# -ZPanel.net
KiCad netlist of a schematic drawn in EAGLE
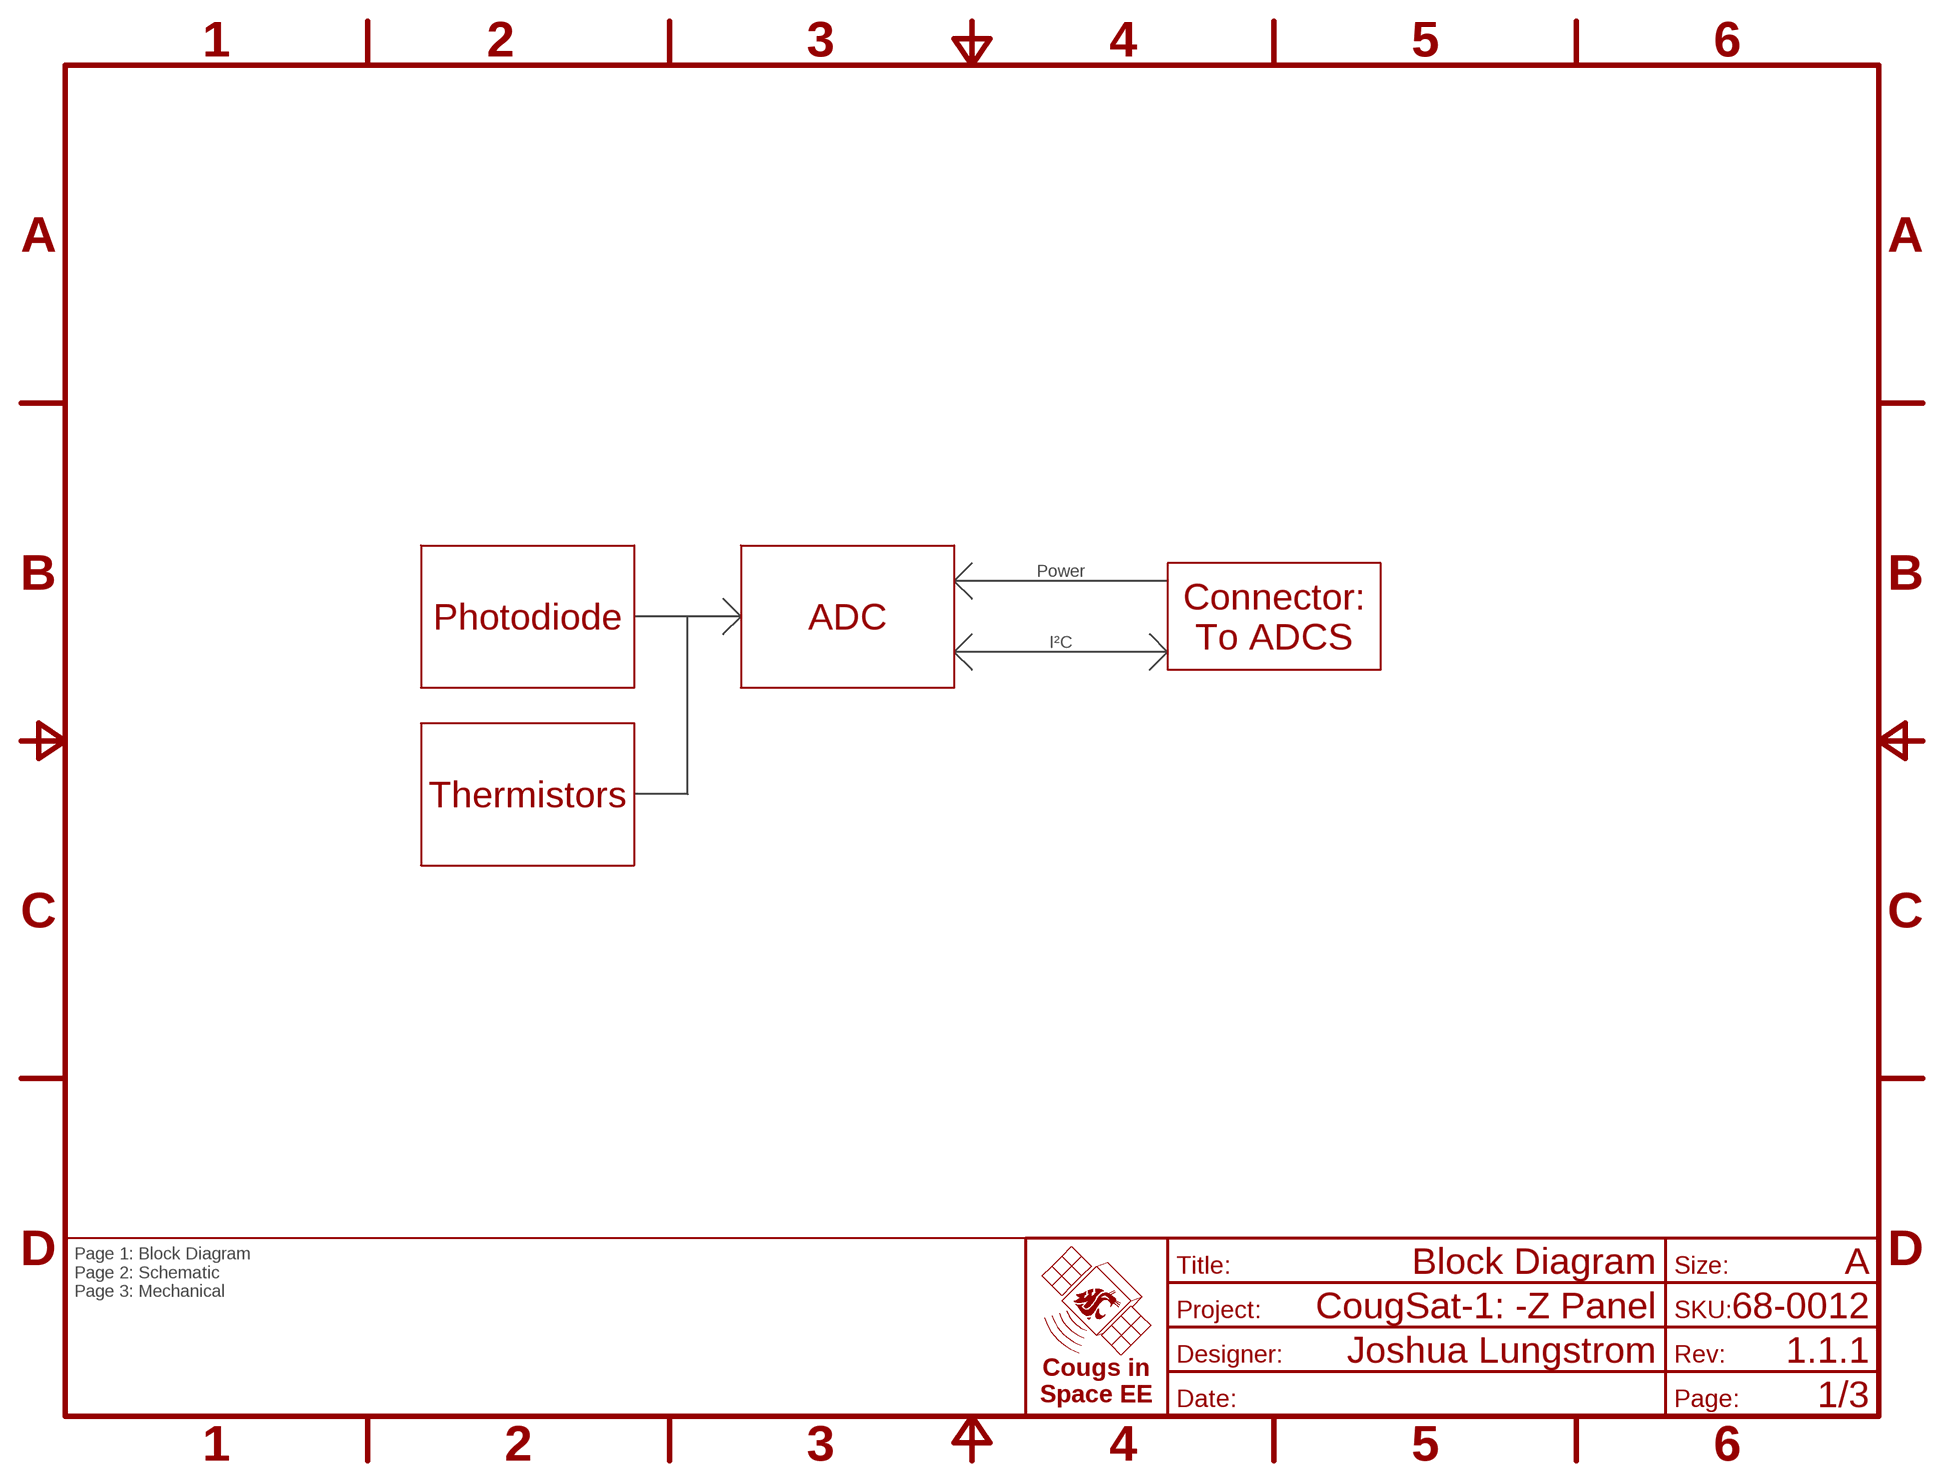
[diagram p0: schematic, sheet 1]
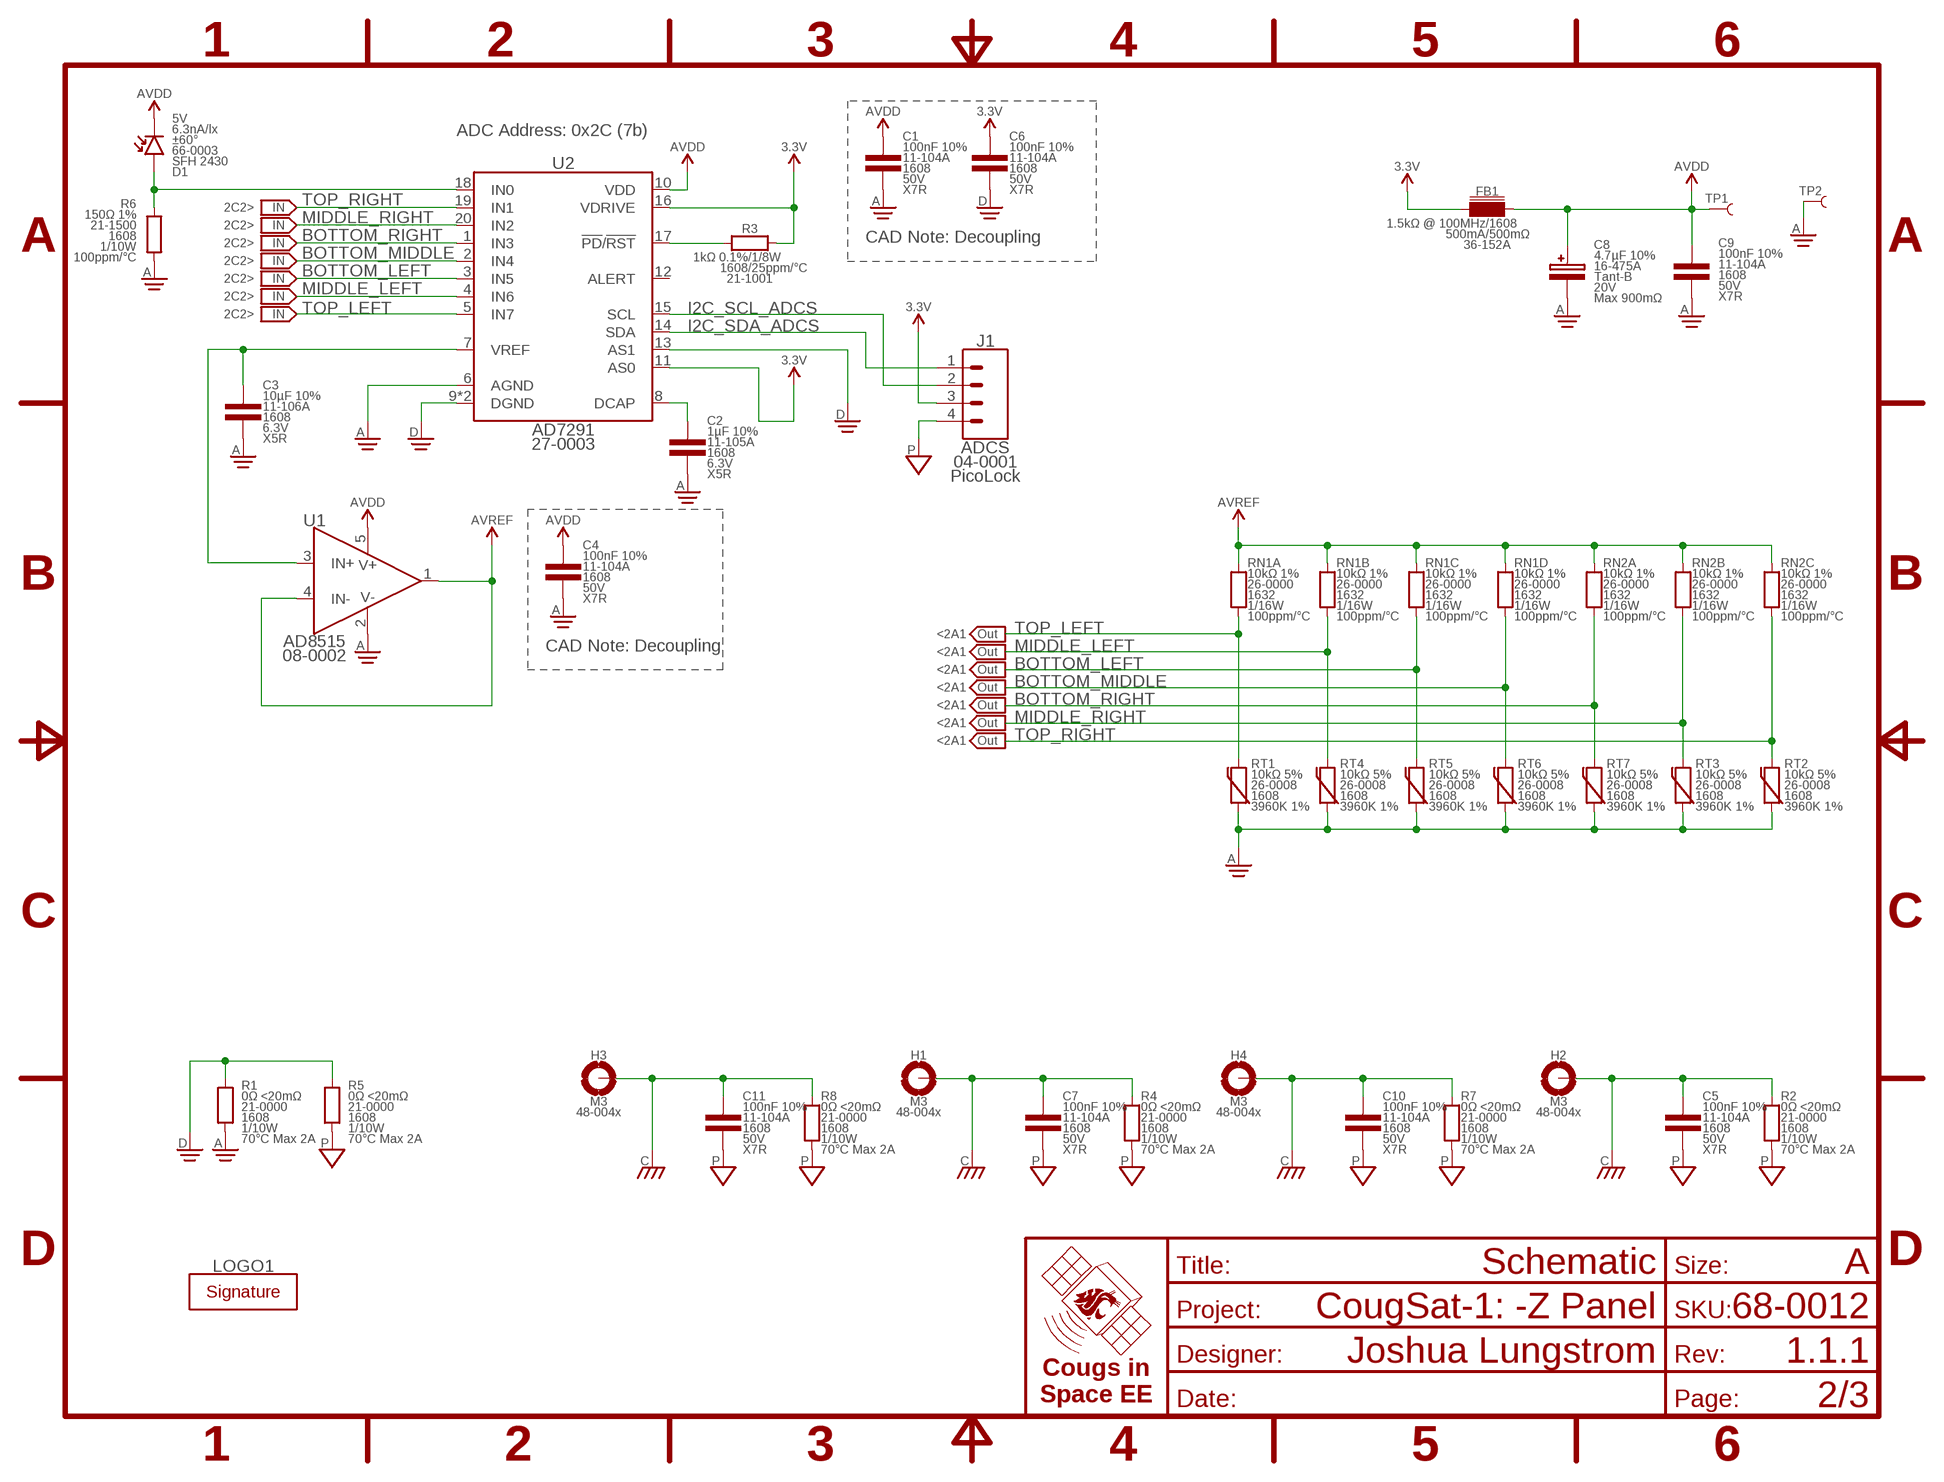
[diagram p1: schematic, sheet 2]
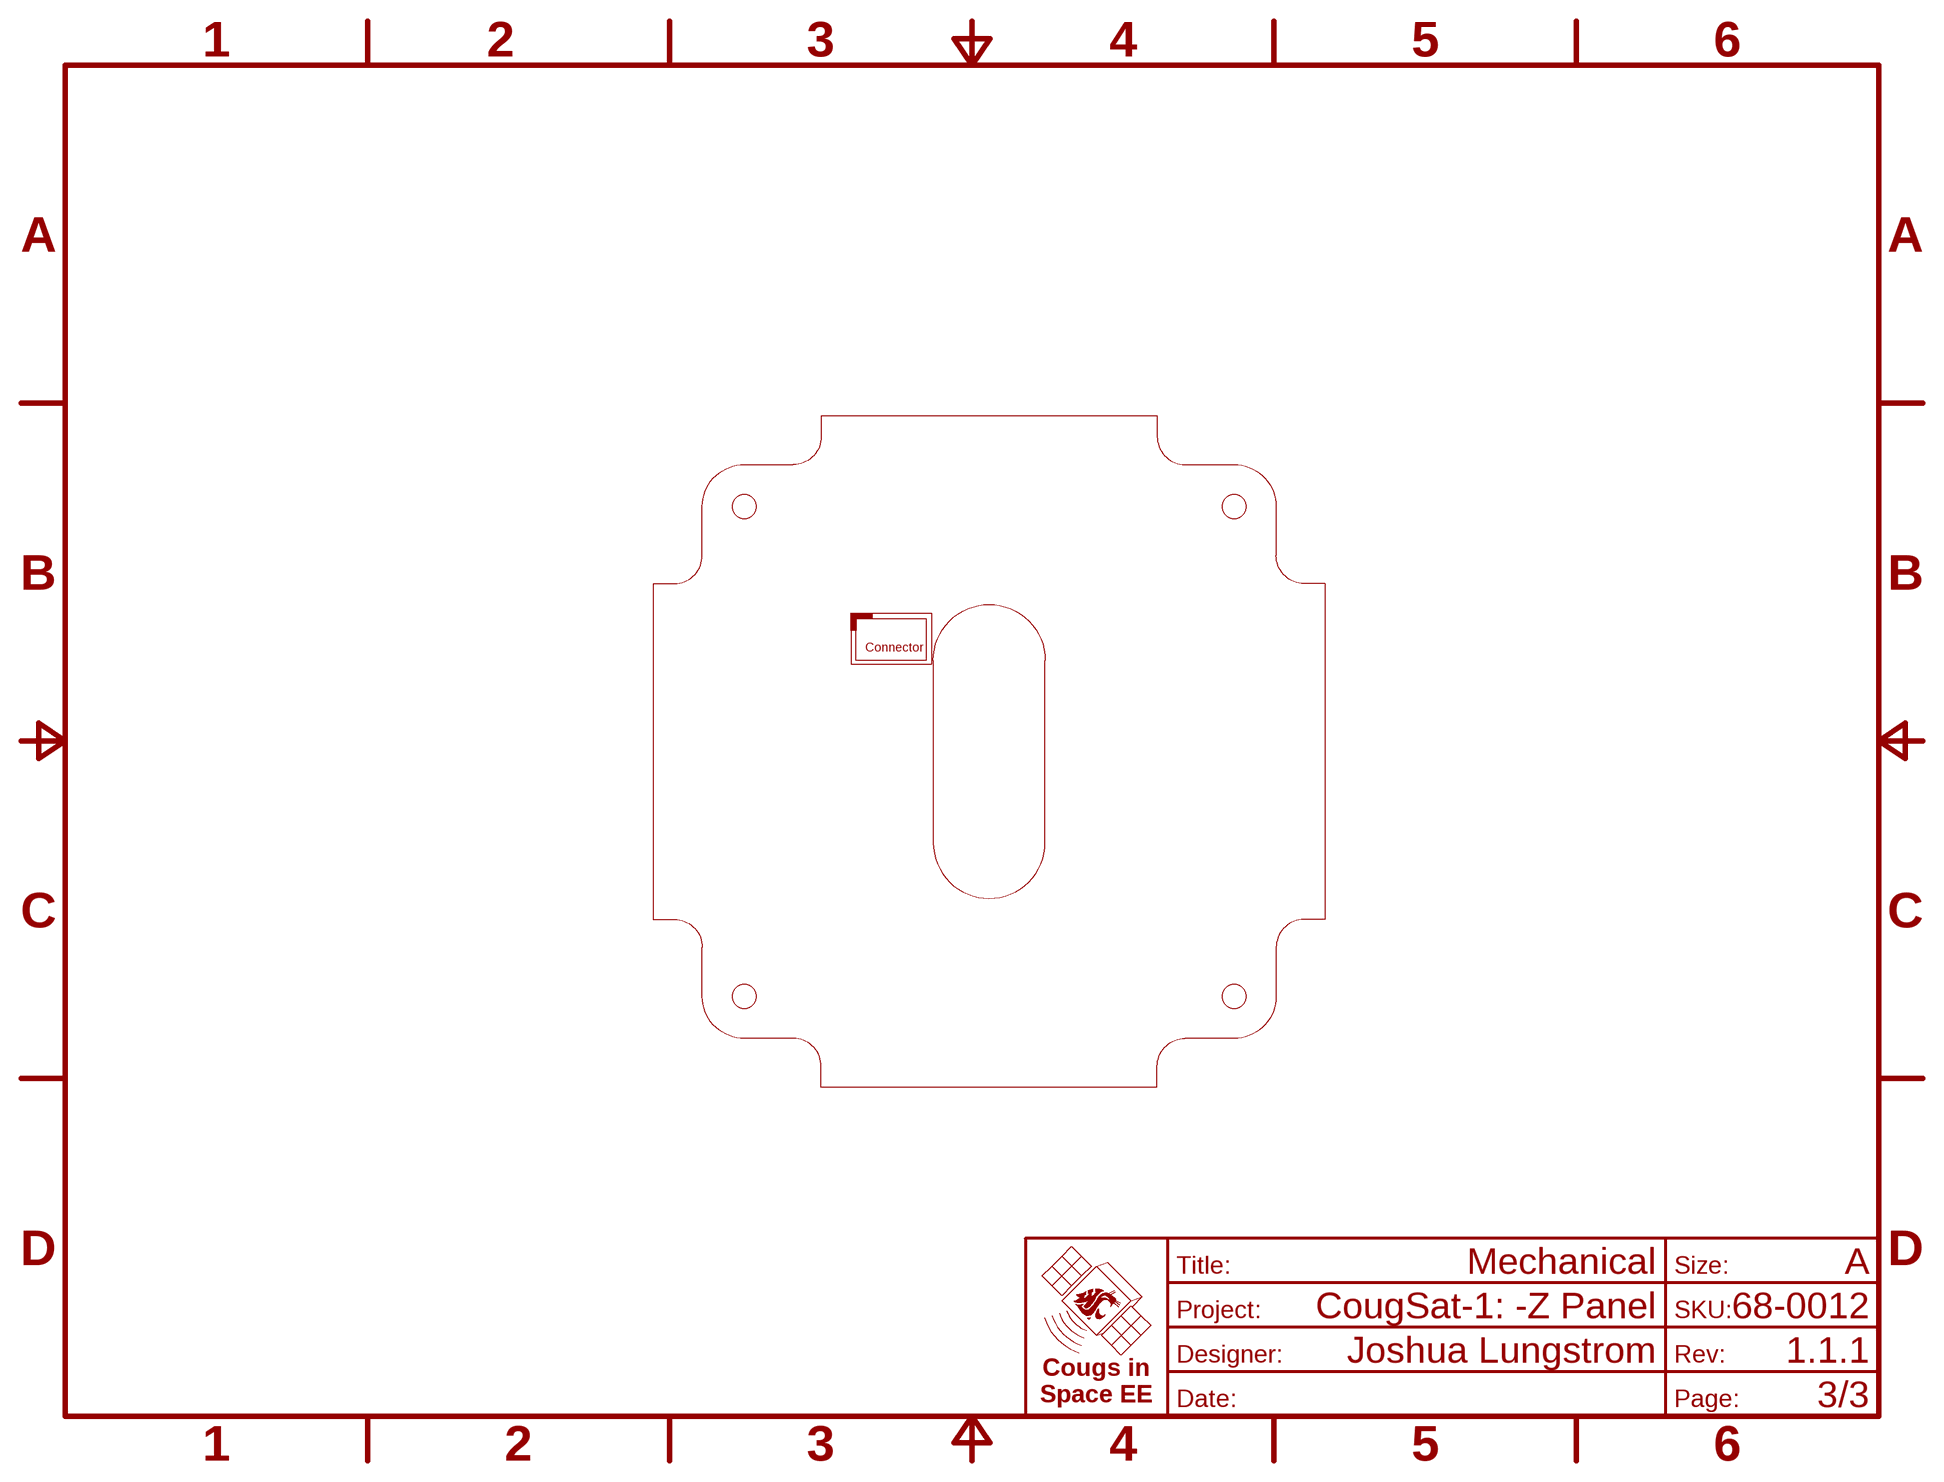
[diagram p2: schematic, sheet 3]

(export (version "E")
  (design (tool "Eeschema 10.0.6"))
  (components
    (comp (ref "C1")
      (value "100nF 10%")
      (footprint "eagle-import:1608")
      (fields
        (field (name "PACKAGE") "1608")
        (field (name "SKU") "11-104A")
        (field (name "TEMP") "X7R")
        (field (name "VOLTAGE") "50V")
      )
      (libsource (lib "eagle-import") (part "CAP-V-1608-100NF"))
    )
    (comp (ref "C2")
      (value "1µF 10%")
      (footprint "eagle-import:1608")
      (fields
        (field (name "PACKAGE") "1608")
        (field (name "SKU") "11-105A")
        (field (name "TEMP") "X5R")
        (field (name "VOLTAGE") "6.3V")
      )
      (libsource (lib "eagle-import") (part "CAP-V-1608-1UF"))
    )
    (comp (ref "C3")
      (value "10µF 10%")
      (footprint "eagle-import:1608")
      (fields
        (field (name "PACKAGE") "1608")
        (field (name "SKU") "11-106A")
        (field (name "TEMP") "X5R")
        (field (name "VOLTAGE") "6.3V")
      )
      (libsource (lib "eagle-import") (part "CAP-V-1608-10UF"))
    )
    (comp (ref "C4")
      (value "100nF 10%")
      (footprint "eagle-import:1608")
      (fields
        (field (name "PACKAGE") "1608")
        (field (name "SKU") "11-104A")
        (field (name "TEMP") "X7R")
        (field (name "VOLTAGE") "50V")
      )
      (libsource (lib "eagle-import") (part "CAP-V-1608-100NF"))
    )
    (comp (ref "C5")
      (value "100nF 10%")
      (footprint "eagle-import:1608")
      (fields
        (field (name "PACKAGE") "1608")
        (field (name "SKU") "11-104A")
        (field (name "TEMP") "X7R")
        (field (name "VOLTAGE") "50V")
      )
      (libsource (lib "eagle-import") (part "CAP-V-1608-100NF"))
    )
    (comp (ref "C6")
      (value "100nF 10%")
      (footprint "eagle-import:1608")
      (fields
        (field (name "PACKAGE") "1608")
        (field (name "SKU") "11-104A")
        (field (name "TEMP") "X7R")
        (field (name "VOLTAGE") "50V")
      )
      (libsource (lib "eagle-import") (part "CAP-V-1608-100NF"))
    )
    (comp (ref "C7")
      (value "100nF 10%")
      (footprint "eagle-import:1608")
      (fields
        (field (name "PACKAGE") "1608")
        (field (name "SKU") "11-104A")
        (field (name "TEMP") "X7R")
        (field (name "VOLTAGE") "50V")
      )
      (libsource (lib "eagle-import") (part "CAP-V-1608-100NF"))
    )
    (comp (ref "C8")
      (value "4.7µF 10%")
      (footprint "eagle-import:4028-POL")
      (fields
        (field (name "ESR") "Max 900mΩ")
        (field (name "PACKAGE") "Tant-B")
        (field (name "SKU") "16-475A")
        (field (name "VOLTAGE") "20V")
      )
      (libsource (lib "eagle-import") (part "CAP-POL-V-4028-4.7UF"))
    )
    (comp (ref "C9")
      (value "100nF 10%")
      (footprint "eagle-import:1608")
      (fields
        (field (name "PACKAGE") "1608")
        (field (name "SKU") "11-104A")
        (field (name "TEMP") "X7R")
        (field (name "VOLTAGE") "50V")
      )
      (libsource (lib "eagle-import") (part "CAP-V-1608-100NF"))
    )
    (comp (ref "C10")
      (value "100nF 10%")
      (footprint "eagle-import:1608")
      (fields
        (field (name "PACKAGE") "1608")
        (field (name "SKU") "11-104A")
        (field (name "TEMP") "X7R")
        (field (name "VOLTAGE") "50V")
      )
      (libsource (lib "eagle-import") (part "CAP-V-1608-100NF"))
    )
    (comp (ref "C11")
      (value "100nF 10%")
      (footprint "eagle-import:1608")
      (fields
        (field (name "PACKAGE") "1608")
        (field (name "SKU") "11-104A")
        (field (name "TEMP") "X7R")
        (field (name "VOLTAGE") "50V")
      )
      (libsource (lib "eagle-import") (part "CAP-V-1608-100NF"))
    )
    (comp (ref "D1")
      (value "SFH 2430")
      (footprint "eagle-import:SFH2430")
      (fields
        (field (name "SKU") "66-0003")
        (field (name "SENSITIVITY") "6.3nA/lx")
        (field (name "VR") "5V")
        (field (name "HALF_ANGLE") "±60°")
      )
      (libsource (lib "eagle-import") (part "PHOTODIODE-SFH2430"))
    )
    (comp (ref "FB1")
      (value "1.5kΩ @ 100MHz")
      (footprint "eagle-import:1608")
      (fields
        (field (name "CURRENT") "500mA")
        (field (name "DCR") "500mΩ")
        (field (name "PACKAGE") "1608")
        (field (name "SKU") "36-152A")
      )
      (libsource (lib "eagle-import") (part "CHOKE-H-1608-1.5K"))
    )
    (comp (ref "H1")
      (value "M3")
      (footprint "eagle-import:MOUNTING_HOLE-3.3")
      (fields (field (name "SKU") "48-004x"))
      (libsource (lib "eagle-import") (part "MOUNTING_HOLE-3.3"))
    )
    (comp (ref "H2")
      (value "M3")
      (footprint "eagle-import:MOUNTING_HOLE-3.3")
      (fields (field (name "SKU") "48-004x"))
      (libsource (lib "eagle-import") (part "MOUNTING_HOLE-3.3"))
    )
    (comp (ref "H3")
      (value "M3")
      (footprint "eagle-import:MOUNTING_HOLE-3.3")
      (fields (field (name "SKU") "48-004x"))
      (libsource (lib "eagle-import") (part "MOUNTING_HOLE-3.3"))
    )
    (comp (ref "H4")
      (value "M3")
      (footprint "eagle-import:MOUNTING_HOLE-3.3")
      (fields (field (name "SKU") "48-004x"))
      (libsource (lib "eagle-import") (part "MOUNTING_HOLE-3.3"))
    )
    (comp (ref "J1")
      (value "ADCS")
      (footprint "eagle-import:PICOLOCK1.5-04")
      (fields (field (name "SKU") "04-0001") (field (name "PACKAGE") "PicoLock"))
      (libsource (lib "eagle-import") (part "1X04-PICOLOCK"))
    )
    (comp (ref "LOGO1")
      (value "SIGNATUREJOSH")
      (footprint "eagle-import:SIGN-JOSH")
      (libsource (lib "eagle-import") (part "SIGNATUREJOSH"))
    )
    (comp (ref "R1")
      (value "0Ω <20mΩ")
      (footprint "eagle-import:1608")
      (fields
        (field (name "PACKAGE") "1608")
        (field (name "POWER") "1/10W")
        (field (name "SKU") "21-0000")
        (field (name "TEMP") "70°C Max 2A")
      )
      (libsource (lib "eagle-import") (part "RES-V-1608-0"))
    )
    (comp (ref "R2")
      (value "0Ω <20mΩ")
      (footprint "eagle-import:1608")
      (fields
        (field (name "PACKAGE") "1608")
        (field (name "POWER") "1/10W")
        (field (name "SKU") "21-0000")
        (field (name "TEMP") "70°C Max 2A")
      )
      (libsource (lib "eagle-import") (part "RES-V-1608-0"))
    )
    (comp (ref "R3")
      (value "1kΩ 0.1%")
      (footprint "eagle-import:1608")
      (fields
        (field (name "PACKAGE") "1608")
        (field (name "POWER") "1/8W")
        (field (name "SKU") "21-1001")
        (field (name "TEMP") "25ppm/°C")
      )
      (libsource (lib "eagle-import") (part "RES-H-1608-1K"))
    )
    (comp (ref "R4")
      (value "0Ω <20mΩ")
      (footprint "eagle-import:1608")
      (fields
        (field (name "PACKAGE") "1608")
        (field (name "POWER") "1/10W")
        (field (name "SKU") "21-0000")
        (field (name "TEMP") "70°C Max 2A")
      )
      (libsource (lib "eagle-import") (part "RES-V-1608-0"))
    )
    (comp (ref "R5")
      (value "0Ω <20mΩ")
      (footprint "eagle-import:1608")
      (fields
        (field (name "PACKAGE") "1608")
        (field (name "POWER") "1/10W")
        (field (name "SKU") "21-0000")
        (field (name "TEMP") "70°C Max 2A")
      )
      (libsource (lib "eagle-import") (part "RES-V-1608-0"))
    )
    (comp (ref "R6")
      (value "150Ω 1%")
      (footprint "eagle-import:1608")
      (fields
        (field (name "PACKAGE") "1608")
        (field (name "POWER") "1/10W")
        (field (name "SKU") "21-1500")
        (field (name "TEMP") "100ppm/°C")
      )
      (libsource (lib "eagle-import") (part "RES-V-1608-150R"))
    )
    (comp (ref "R7")
      (value "0Ω <20mΩ")
      (footprint "eagle-import:1608")
      (fields
        (field (name "PACKAGE") "1608")
        (field (name "POWER") "1/10W")
        (field (name "SKU") "21-0000")
        (field (name "TEMP") "70°C Max 2A")
      )
      (libsource (lib "eagle-import") (part "RES-V-1608-0"))
    )
    (comp (ref "R8")
      (value "0Ω <20mΩ")
      (footprint "eagle-import:1608")
      (fields
        (field (name "PACKAGE") "1608")
        (field (name "POWER") "1/10W")
        (field (name "SKU") "21-0000")
        (field (name "TEMP") "70°C Max 2A")
      )
      (libsource (lib "eagle-import") (part "RES-V-1608-0"))
    )
    (comp (ref "RN1")
      (value "10kΩ 1%")
      (footprint "eagle-import:1632")
      (fields
        (field (name "PACKAGE") "1632")
        (field (name "POWER") "1/16W")
        (field (name "SKU") "26-0000")
        (field (name "TEMP") "100ppm/°C")
      )
      (libsource (lib "eagle-import") (part "RES-4-V-1632-10K"))
    )
    (comp (ref "RN2")
      (value "10kΩ 1%")
      (footprint "eagle-import:1632")
      (fields
        (field (name "PACKAGE") "1632")
        (field (name "POWER") "1/16W")
        (field (name "SKU") "26-0000")
        (field (name "TEMP") "100ppm/°C")
      )
      (libsource (lib "eagle-import") (part "RES-4-V-1632-10K"))
    )
    (comp (ref "RT1")
      (value "10kΩ 5%")
      (footprint "eagle-import:1608")
      (fields
        (field (name "B2585") "3960K 1%")
        (field (name "PACKAGE") "1608")
        (field (name "SKU") "26-0008")
      )
      (libsource (lib "eagle-import") (part "THERMISTOR-V-1608-10K"))
    )
    (comp (ref "RT2")
      (value "10kΩ 5%")
      (footprint "eagle-import:1608")
      (fields
        (field (name "B2585") "3960K 1%")
        (field (name "PACKAGE") "1608")
        (field (name "SKU") "26-0008")
      )
      (libsource (lib "eagle-import") (part "THERMISTOR-V-1608-10K"))
    )
    (comp (ref "RT3")
      (value "10kΩ 5%")
      (footprint "eagle-import:1608")
      (fields
        (field (name "B2585") "3960K 1%")
        (field (name "PACKAGE") "1608")
        (field (name "SKU") "26-0008")
      )
      (libsource (lib "eagle-import") (part "THERMISTOR-V-1608-10K"))
    )
    (comp (ref "RT4")
      (value "10kΩ 5%")
      (footprint "eagle-import:1608")
      (fields
        (field (name "B2585") "3960K 1%")
        (field (name "PACKAGE") "1608")
        (field (name "SKU") "26-0008")
      )
      (libsource (lib "eagle-import") (part "THERMISTOR-V-1608-10K"))
    )
    (comp (ref "RT5")
      (value "10kΩ 5%")
      (footprint "eagle-import:1608")
      (fields
        (field (name "B2585") "3960K 1%")
        (field (name "PACKAGE") "1608")
        (field (name "SKU") "26-0008")
      )
      (libsource (lib "eagle-import") (part "THERMISTOR-V-1608-10K"))
    )
    (comp (ref "RT6")
      (value "10kΩ 5%")
      (footprint "eagle-import:1608")
      (fields
        (field (name "B2585") "3960K 1%")
        (field (name "PACKAGE") "1608")
        (field (name "SKU") "26-0008")
      )
      (libsource (lib "eagle-import") (part "THERMISTOR-V-1608-10K"))
    )
    (comp (ref "RT7")
      (value "10kΩ 5%")
      (footprint "eagle-import:1608")
      (fields
        (field (name "B2585") "3960K 1%")
        (field (name "PACKAGE") "1608")
        (field (name "SKU") "26-0008")
      )
      (libsource (lib "eagle-import") (part "THERMISTOR-V-1608-10K"))
    )
    (comp (ref "TP1")
      (value "TEST_POINT-THT-0.7")
      (footprint "eagle-import:THT-0.7")
      (libsource (lib "eagle-import") (part "TEST_POINT-THT-0.7"))
    )
    (comp (ref "TP2")
      (value "TEST_POINT-THT-0.7")
      (footprint "eagle-import:THT-0.7")
      (libsource (lib "eagle-import") (part "TEST_POINT-THT-0.7"))
    )
    (comp (ref "U1")
      (value "AD8515")
      (footprint "eagle-import:SOT23-5")
      (fields (field (name "SKU") "08-0002"))
      (libsource (lib "eagle-import") (part "OPAMP-1-AD8515"))
    )
    (comp (ref "U2")
      (value "AD7291")
      (footprint "eagle-import:QFN-20-4040")
      (fields (field (name "SKU") "27-0003"))
      (libsource (lib "eagle-import") (part "AD7291"))
    )
  )
  (nets
    (net (code "1") (name "3.3V") (class "Default")
      (node (ref "C6") (pin "1") (pinfunction "1_1") (pintype "passive"))
      (node (ref "FB1") (pin "1") (pinfunction "1_1") (pintype "passive"))
      (node (ref "J1") (pin "3") (pinfunction "3_3") (pintype "passive"))
      (node (ref "R3") (pin "2") (pinfunction "2_2") (pintype "passive"))
      (node (ref "U2") (pin "11") (pinfunction "AS0_11") (pintype "passive"))
      (node (ref "U2") (pin "16") (pinfunction "VDRIVE_16") (pintype "power_in"))
    )
    (net (code "2") (name "AGND") (class "Default")
      (node (ref "C1") (pin "2") (pinfunction "2_2") (pintype "passive"))
      (node (ref "C2") (pin "2") (pinfunction "2_2") (pintype "passive"))
      (node (ref "C3") (pin "2") (pinfunction "2_2") (pintype "passive"))
      (node (ref "C4") (pin "2") (pinfunction "2_2") (pintype "passive"))
      (node (ref "C8") (pin "C") (pinfunction "C_C") (pintype "passive"))
      (node (ref "C9") (pin "2") (pinfunction "2_2") (pintype "passive"))
      (node (ref "R1") (pin "1") (pinfunction "1_1") (pintype "passive"))
      (node (ref "R6") (pin "1") (pinfunction "1_1") (pintype "passive"))
      (node (ref "RT1") (pin "1") (pinfunction "1_1") (pintype "passive"))
      (node (ref "RT2") (pin "1") (pinfunction "1_1") (pintype "passive"))
      (node (ref "RT3") (pin "1") (pinfunction "1_1") (pintype "passive"))
      (node (ref "RT4") (pin "1") (pinfunction "1_1") (pintype "passive"))
      (node (ref "RT5") (pin "1") (pinfunction "1_1") (pintype "passive"))
      (node (ref "RT6") (pin "1") (pinfunction "1_1") (pintype "passive"))
      (node (ref "RT7") (pin "1") (pinfunction "1_1") (pintype "passive"))
      (node (ref "TP2") (pin "1") (pinfunction "1_1") (pintype "passive"))
      (node (ref "U1") (pin "2") (pinfunction "V-_2") (pintype "power_in"))
      (node (ref "U2") (pin "6") (pinfunction "AGND_6") (pintype "power_in"))
    )
    (net (code "3") (name "AVDD") (class "Default")
      (node (ref "C1") (pin "1") (pinfunction "1_1") (pintype "passive"))
      (node (ref "C4") (pin "1") (pinfunction "1_1") (pintype "passive"))
      (node (ref "C8") (pin "A") (pinfunction "A_A") (pintype "passive"))
      (node (ref "C9") (pin "1") (pinfunction "1_1") (pintype "passive"))
      (node (ref "D1") (pin "C") (pinfunction "C_C") (pintype "passive"))
      (node (ref "FB1") (pin "2") (pinfunction "2_2") (pintype "passive"))
      (node (ref "TP1") (pin "1") (pinfunction "1_1") (pintype "passive"))
      (node (ref "U1") (pin "5") (pinfunction "V+_5") (pintype "power_in"))
      (node (ref "U2") (pin "10") (pinfunction "VDD_10") (pintype "power_in"))
    )
    (net (code "4") (name "AVREF") (class "Default")
      (node (ref "RN1") (pin "5") (pinfunction "2_5") (pintype "passive"))
      (node (ref "RN1") (pin "6") (pinfunction "2_6") (pintype "passive"))
      (node (ref "RN1") (pin "7") (pinfunction "2_7") (pintype "passive"))
      (node (ref "RN1") (pin "8") (pinfunction "2_8") (pintype "passive"))
      (node (ref "RN2") (pin "6") (pinfunction "2_6") (pintype "passive"))
      (node (ref "RN2") (pin "7") (pinfunction "2_7") (pintype "passive"))
      (node (ref "RN2") (pin "8") (pinfunction "2_8") (pintype "passive"))
      (node (ref "U1") (pin "1") (pinfunction "OUT_1") (pintype "output"))
      (node (ref "U1") (pin "4") (pinfunction "IN-_4") (pintype "passive"))
    )
    (net (code "5") (name "BOTTOM_LEFT") (class "Default")
      (node (ref "RN1") (pin "3") (pinfunction "1_3") (pintype "passive"))
      (node (ref "RT5") (pin "2") (pinfunction "2_2") (pintype "passive"))
      (node (ref "U2") (pin "3") (pinfunction "IN5_3") (pintype "input"))
    )
    (net (code "6") (name "BOTTOM_MIDDLE") (class "Default")
      (node (ref "RN1") (pin "4") (pinfunction "1_4") (pintype "passive"))
      (node (ref "RT6") (pin "2") (pinfunction "2_2") (pintype "passive"))
      (node (ref "U2") (pin "2") (pinfunction "IN4_2") (pintype "input"))
    )
    (net (code "7") (name "BOTTOM_RIGHT") (class "Default")
      (node (ref "RN2") (pin "1") (pinfunction "1_1") (pintype "passive"))
      (node (ref "RT7") (pin "2") (pinfunction "2_2") (pintype "passive"))
      (node (ref "U2") (pin "1") (pinfunction "IN3_1") (pintype "input"))
    )
    (net (code "8") (name "CHASSIS") (class "Default")
      (node (ref "C10") (pin "1") (pinfunction "1_1") (pintype "passive"))
      (node (ref "C11") (pin "1") (pinfunction "1_1") (pintype "passive"))
      (node (ref "C5") (pin "1") (pinfunction "1_1") (pintype "passive"))
      (node (ref "C7") (pin "1") (pinfunction "1_1") (pintype "passive"))
      (node (ref "H1") (pin "1") (pinfunction "MOUNT_1") (pintype "passive"))
      (node (ref "H1") (pin "V1") (pinfunction "MOUNT_V1") (pintype "passive"))
      (node (ref "H1") (pin "V10") (pinfunction "MOUNT_V10") (pintype "passive"))
      (node (ref "H1") (pin "V2") (pinfunction "MOUNT_V2") (pintype "passive"))
      (node (ref "H1") (pin "V3") (pinfunction "MOUNT_V3") (pintype "passive"))
      (node (ref "H1") (pin "V4") (pinfunction "MOUNT_V4") (pintype "passive"))
      (node (ref "H1") (pin "V5") (pinfunction "MOUNT_V5") (pintype "passive"))
      (node (ref "H1") (pin "V6") (pinfunction "MOUNT_V6") (pintype "passive"))
      (node (ref "H1") (pin "V7") (pinfunction "MOUNT_V7") (pintype "passive"))
      (node (ref "H1") (pin "V8") (pinfunction "MOUNT_V8") (pintype "passive"))
      (node (ref "H1") (pin "V9") (pinfunction "MOUNT_V9") (pintype "passive"))
      (node (ref "H2") (pin "1") (pinfunction "MOUNT_1") (pintype "passive"))
      (node (ref "H2") (pin "V1") (pinfunction "MOUNT_V1") (pintype "passive"))
      (node (ref "H2") (pin "V10") (pinfunction "MOUNT_V10") (pintype "passive"))
      (node (ref "H2") (pin "V2") (pinfunction "MOUNT_V2") (pintype "passive"))
      (node (ref "H2") (pin "V3") (pinfunction "MOUNT_V3") (pintype "passive"))
      (node (ref "H2") (pin "V4") (pinfunction "MOUNT_V4") (pintype "passive"))
      (node (ref "H2") (pin "V5") (pinfunction "MOUNT_V5") (pintype "passive"))
      (node (ref "H2") (pin "V6") (pinfunction "MOUNT_V6") (pintype "passive"))
      (node (ref "H2") (pin "V7") (pinfunction "MOUNT_V7") (pintype "passive"))
      (node (ref "H2") (pin "V8") (pinfunction "MOUNT_V8") (pintype "passive"))
      (node (ref "H2") (pin "V9") (pinfunction "MOUNT_V9") (pintype "passive"))
      (node (ref "H3") (pin "1") (pinfunction "MOUNT_1") (pintype "passive"))
      (node (ref "H3") (pin "V1") (pinfunction "MOUNT_V1") (pintype "passive"))
      (node (ref "H3") (pin "V10") (pinfunction "MOUNT_V10") (pintype "passive"))
      (node (ref "H3") (pin "V2") (pinfunction "MOUNT_V2") (pintype "passive"))
      (node (ref "H3") (pin "V3") (pinfunction "MOUNT_V3") (pintype "passive"))
      (node (ref "H3") (pin "V4") (pinfunction "MOUNT_V4") (pintype "passive"))
      (node (ref "H3") (pin "V5") (pinfunction "MOUNT_V5") (pintype "passive"))
      (node (ref "H3") (pin "V6") (pinfunction "MOUNT_V6") (pintype "passive"))
      (node (ref "H3") (pin "V7") (pinfunction "MOUNT_V7") (pintype "passive"))
      (node (ref "H3") (pin "V8") (pinfunction "MOUNT_V8") (pintype "passive"))
      (node (ref "H3") (pin "V9") (pinfunction "MOUNT_V9") (pintype "passive"))
      (node (ref "H4") (pin "1") (pinfunction "MOUNT_1") (pintype "passive"))
      (node (ref "H4") (pin "V1") (pinfunction "MOUNT_V1") (pintype "passive"))
      (node (ref "H4") (pin "V10") (pinfunction "MOUNT_V10") (pintype "passive"))
      (node (ref "H4") (pin "V2") (pinfunction "MOUNT_V2") (pintype "passive"))
      (node (ref "H4") (pin "V3") (pinfunction "MOUNT_V3") (pintype "passive"))
      (node (ref "H4") (pin "V4") (pinfunction "MOUNT_V4") (pintype "passive"))
      (node (ref "H4") (pin "V5") (pinfunction "MOUNT_V5") (pintype "passive"))
      (node (ref "H4") (pin "V6") (pinfunction "MOUNT_V6") (pintype "passive"))
      (node (ref "H4") (pin "V7") (pinfunction "MOUNT_V7") (pintype "passive"))
      (node (ref "H4") (pin "V8") (pinfunction "MOUNT_V8") (pintype "passive"))
      (node (ref "H4") (pin "V9") (pinfunction "MOUNT_V9") (pintype "passive"))
      (node (ref "R2") (pin "2") (pinfunction "2_2") (pintype "passive"))
      (node (ref "R4") (pin "2") (pinfunction "2_2") (pintype "passive"))
      (node (ref "R7") (pin "2") (pinfunction "2_2") (pintype "passive"))
      (node (ref "R8") (pin "2") (pinfunction "2_2") (pintype "passive"))
    )
    (net (code "9") (name "DGND") (class "Default")
      (node (ref "C6") (pin "2") (pinfunction "2_2") (pintype "passive"))
      (node (ref "R1") (pin "2") (pinfunction "2_2") (pintype "passive"))
      (node (ref "R5") (pin "2") (pinfunction "2_2") (pintype "passive"))
      (node (ref "U2") (pin "13") (pinfunction "AS1_13") (pintype "passive"))
      (node (ref "U2") (pin "9") (pinfunction "DGND_9") (pintype "power_in"))
      (node (ref "U2") (pin "PAD") (pinfunction "DGND_PAD") (pintype "power_in"))
    )
    (net (code "10") (name "I2C_SCL_ADCS") (class "Default")
      (node (ref "J1") (pin "2") (pinfunction "2_2") (pintype "passive"))
      (node (ref "U2") (pin "15") (pinfunction "SCL_15") (pintype "input"))
    )
    (net (code "11") (name "I2C_SDA_ADCS") (class "Default")
      (node (ref "J1") (pin "1") (pinfunction "1_1") (pintype "passive"))
      (node (ref "U2") (pin "14") (pinfunction "SDA_14") (pintype "bidirectional"))
    )
    (net (code "12") (name "MIDDLE_LEFT") (class "Default")
      (node (ref "RN1") (pin "2") (pinfunction "1_2") (pintype "passive"))
      (node (ref "RT4") (pin "2") (pinfunction "2_2") (pintype "passive"))
      (node (ref "U2") (pin "4") (pinfunction "IN6_4") (pintype "input"))
    )
    (net (code "13") (name "MIDDLE_RIGHT") (class "Default")
      (node (ref "RN2") (pin "2") (pinfunction "1_2") (pintype "passive"))
      (node (ref "RT3") (pin "2") (pinfunction "2_2") (pintype "passive"))
      (node (ref "U2") (pin "20") (pinfunction "IN2_20") (pintype "input"))
    )
    (net (code "14") (name "Net-(U1-IN+)") (class "Default")
      (node (ref "C3") (pin "1") (pinfunction "1_1") (pintype "passive"))
      (node (ref "U1") (pin "3") (pinfunction "IN+_3") (pintype "passive"))
      (node (ref "U2") (pin "7") (pinfunction "VREF_7") (pintype "bidirectional"))
    )
    (net (code "15") (name "Net-(U2-DCAP)") (class "Default")
      (node (ref "C2") (pin "1") (pinfunction "1_1") (pintype "passive"))
      (node (ref "U2") (pin "8") (pinfunction "DCAP_8") (pintype "passive"))
    )
    (net (code "16") (name "Net-(U2-IN0)") (class "Default")
      (node (ref "D1") (pin "A") (pinfunction "A_A") (pintype "passive"))
      (node (ref "R6") (pin "2") (pinfunction "2_2") (pintype "passive"))
      (node (ref "U2") (pin "18") (pinfunction "IN0_18") (pintype "input"))
    )
    (net (code "17") (name "Net-(U2-~{PD}{slash}~{RST})") (class "Default")
      (node (ref "R3") (pin "1") (pinfunction "1_1") (pintype "passive"))
      (node (ref "U2") (pin "17") (pinfunction "~{PD}/~{RST}_17") (pintype "input"))
    )
    (net (code "18") (name "PGND") (class "Default")
      (node (ref "C10") (pin "2") (pinfunction "2_2") (pintype "passive"))
      (node (ref "C11") (pin "2") (pinfunction "2_2") (pintype "passive"))
      (node (ref "C5") (pin "2") (pinfunction "2_2") (pintype "passive"))
      (node (ref "C7") (pin "2") (pinfunction "2_2") (pintype "passive"))
      (node (ref "J1") (pin "4") (pinfunction "4_4") (pintype "passive"))
      (node (ref "R2") (pin "1") (pinfunction "1_1") (pintype "passive"))
      (node (ref "R4") (pin "1") (pinfunction "1_1") (pintype "passive"))
      (node (ref "R5") (pin "1") (pinfunction "1_1") (pintype "passive"))
      (node (ref "R7") (pin "1") (pinfunction "1_1") (pintype "passive"))
      (node (ref "R8") (pin "1") (pinfunction "1_1") (pintype "passive"))
    )
    (net (code "19") (name "TOP_LEFT") (class "Default")
      (node (ref "RN1") (pin "1") (pinfunction "1_1") (pintype "passive"))
      (node (ref "RT1") (pin "2") (pinfunction "2_2") (pintype "passive"))
      (node (ref "U2") (pin "5") (pinfunction "IN7_5") (pintype "input"))
    )
    (net (code "20") (name "TOP_RIGHT") (class "Default")
      (node (ref "RN2") (pin "3") (pinfunction "1_3") (pintype "passive"))
      (node (ref "RT2") (pin "2") (pinfunction "2_2") (pintype "passive"))
      (node (ref "U2") (pin "19") (pinfunction "IN1_19") (pintype "input"))
    )
    (net (code "21") (name "unconnected-(U2-ALERT-Pad12)") (class "Default")
      (node (ref "U2") (pin "12") (pinfunction "ALERT_12") (pintype "output"))
    )
  )
)
